# CAN_1.net
KiCad netlist of a schematic drawn in Altium Designer
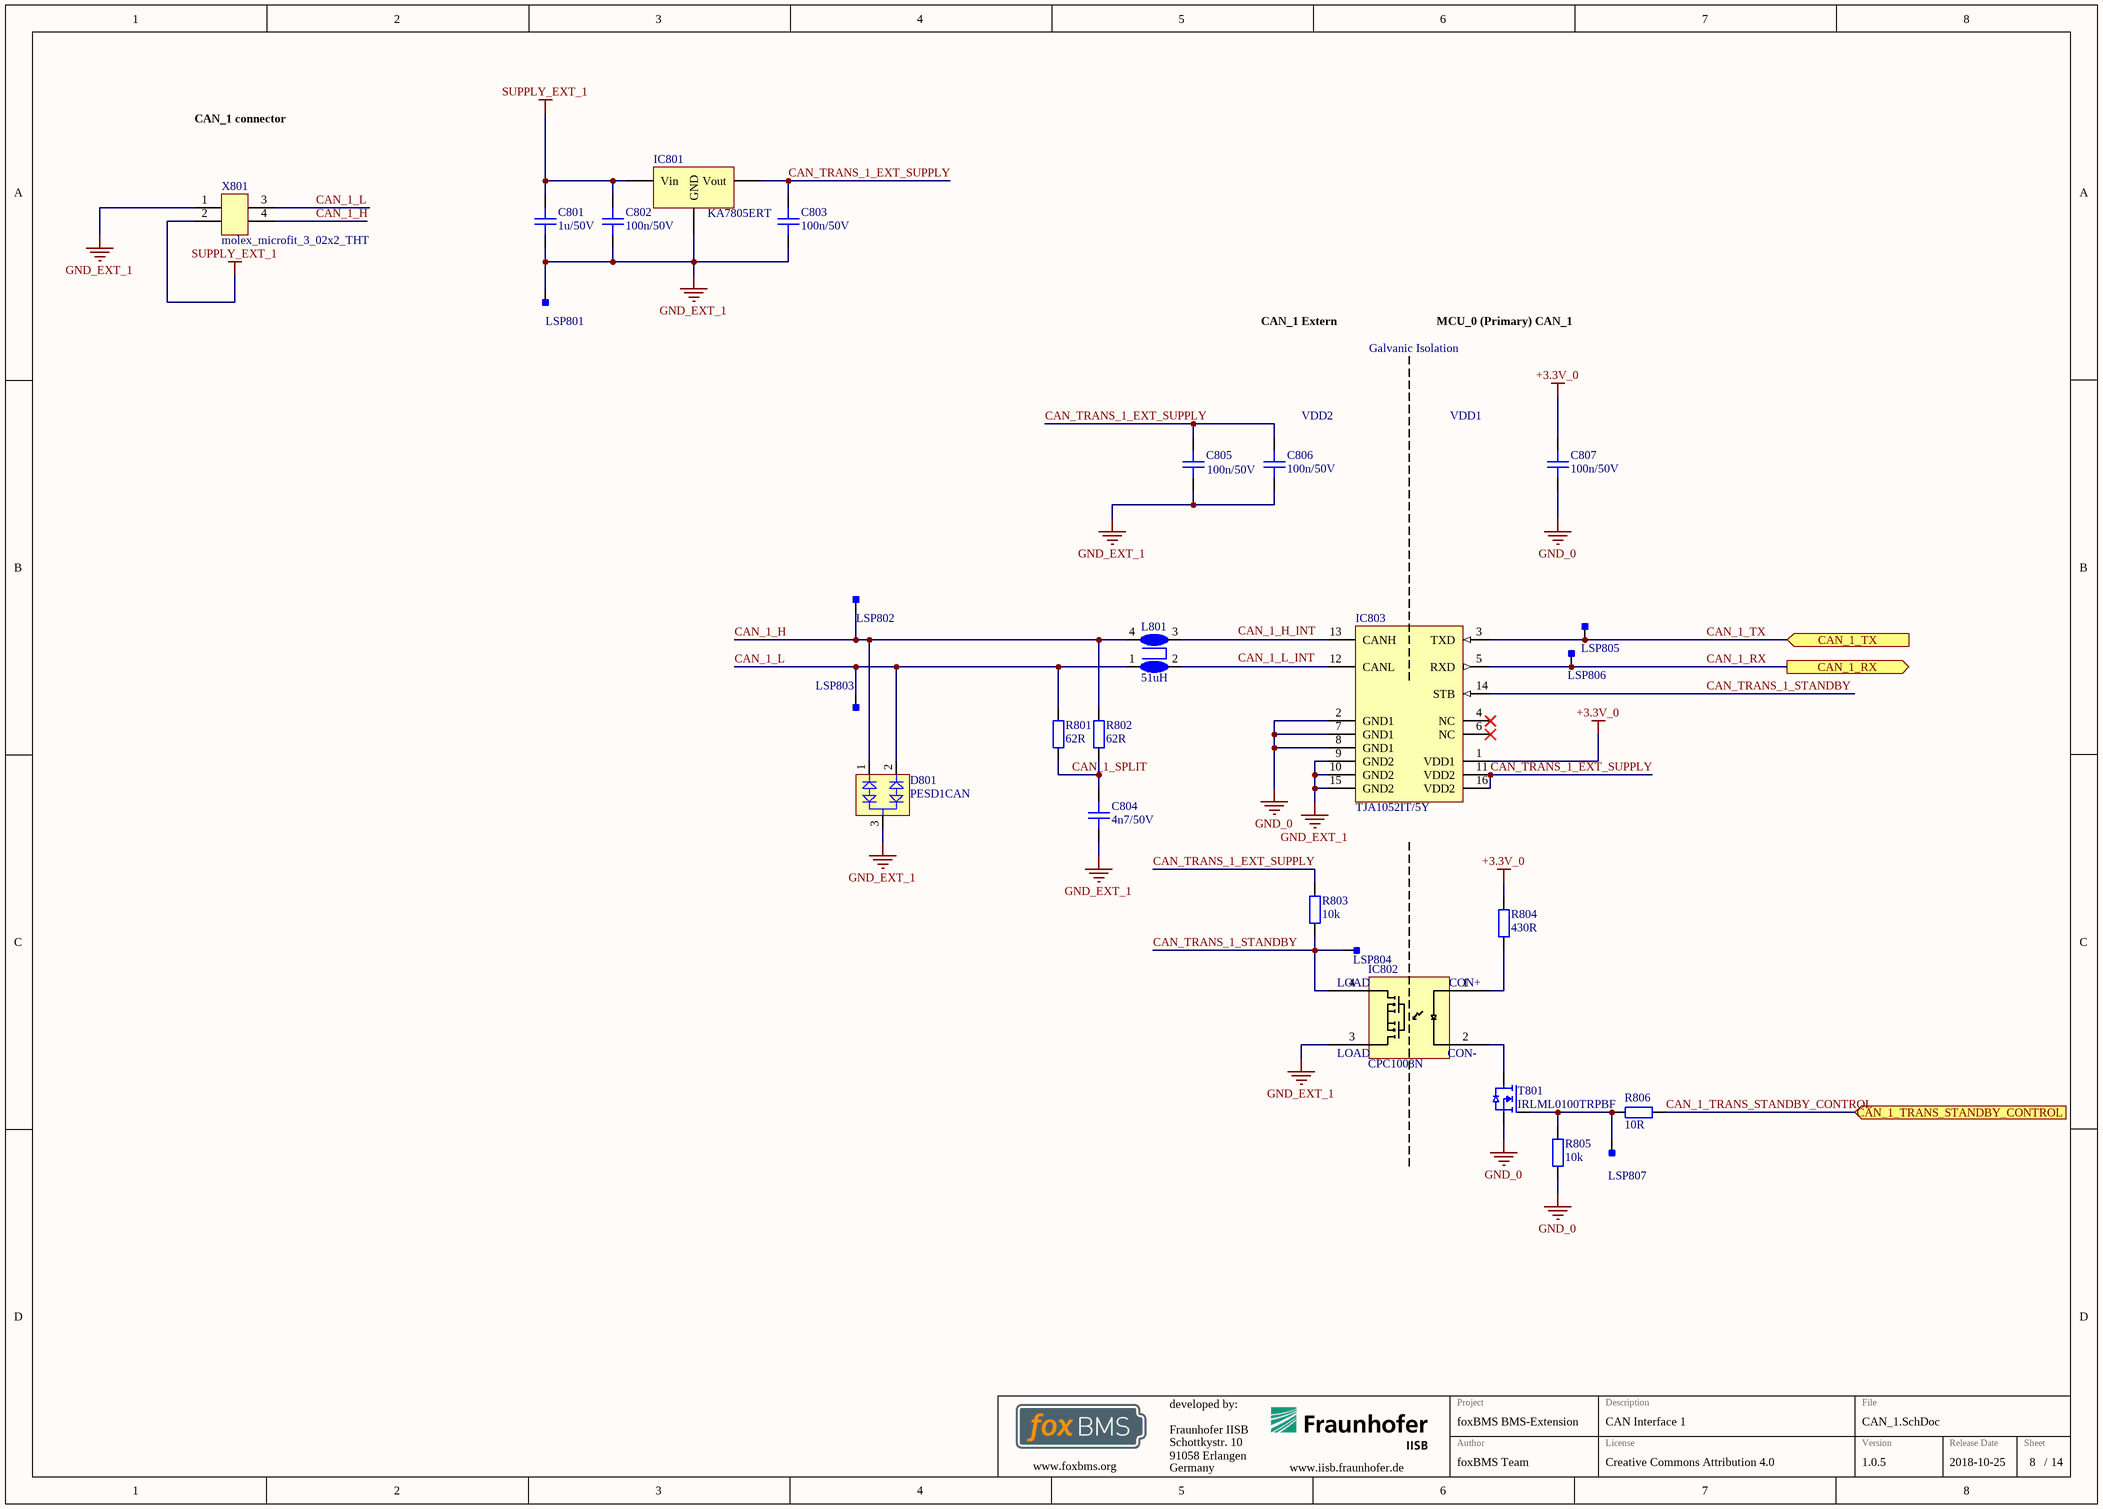
[diagram p0: CAN_1.SchDoc]

(export (version "E")
  (design (tool "Eeschema 10.0.6"))
  (components
    (comp (ref "C801")
      (value "1u/50V")
      (footprint "CAPC1608X08N")
      (description "MLCC")
      (fields (field (name "PART NUMBER") "gen_C_ceramic_1u_50V_X7R_0603") (field (name "TOLERANCE") "± 10%"))
      (libsource (lib "OE750") (part "C"))
    )
    (comp (ref "C802")
      (value "100n/50V")
      (footprint "CAPC1608X08N")
      (description "MLCC")
      (fields (field (name "PART NUMBER") "gen_C_ceramic_100n_50V_X7R_0603"))
      (libsource (lib "OE750") (part "C"))
    )
    (comp (ref "C803")
      (value "100n/50V")
      (footprint "CAPC1608X08N")
      (description "MLCC")
      (fields (field (name "PART NUMBER") "gen_C_ceramic_100n_50V_X7R_0603"))
      (libsource (lib "OE750") (part "C"))
    )
    (comp (ref "C804")
      (value "4n7/50V")
      (footprint "CAPC1608X08N")
      (description "MLCC")
      (fields (field (name "PART NUMBER") "gen_C_ceramic_4n7_50V_X7R_0603"))
      (libsource (lib "OE750") (part "C"))
    )
    (comp (ref "C805")
      (value "100n/50V")
      (footprint "CAPC1608X08N")
      (description "MLCC")
      (fields (field (name "PART NUMBER") "gen_C_ceramic_100n_50V_X7R_0603"))
      (libsource (lib "OE750") (part "C"))
    )
    (comp (ref "C806")
      (value "100n/50V")
      (footprint "CAPC1608X08N")
      (description "MLCC")
      (fields (field (name "PART NUMBER") "gen_C_ceramic_100n_50V_X7R_0603"))
      (libsource (lib "OE750") (part "C"))
    )
    (comp (ref "C807")
      (value "100n/50V")
      (footprint "CAPC1608X08N")
      (description "MLCC")
      (fields (field (name "PART NUMBER") "gen_C_ceramic_100n_50V_X7R_0603"))
      (libsource (lib "OE750") (part "C"))
    )
    (comp (ref "D801")
      (value "PESD1CAN")
      (footprint "NXP-SOT23-3_V")
      (description "CAN Bus ESD Protection Diode, 200 W, 24 V, -65 to 150 degC, 3-Pin SOT23, RoHS, Tape and Reel")
      (fields (field (name "MANUFACTURER") "NXP Semiconductors"))
      (libsource (lib "Altium Content Vault") (part "NXP-PESD1CAN-SOT23-3"))
    )
    (comp (ref "IC801")
      (value "KA7805ERT")
      (footprint "DPAK228P950X240-3N")
      (description "3-Terminal 1 A Positive Voltage Regulator")
      (fields (field (name "PART NUMBER") "KA7805ERTF") (field (name "MANUFACTURER") "Fairchild"))
      (libsource (lib "OE750") (part "KA7805ERT"))
    )
    (comp (ref "IC802")
      (value "CPC1008N")
      (footprint "SOP254P610X218-4N")
      (description "Single-Pole, Normally Open 4-Pin SOP OptoMOS Relay")
      (fields (field (name "MANUFACTURER") "CLARE"))
      (libsource (lib "OE750") (part "CPC1008N"))
    )
    (comp (ref "IC803")
      (value "TJA1052IT/5Y")
      (footprint "NXP-SOIC-16_L")
      (fields (field (name "MANUFACTURER") "NXPSemiconductors"))
      (libsource (lib "Altium Content Vault") (part "NXP-TJA1052IT-SOIC-16"))
    )
    (comp (ref "L801")
      (value "51uH")
      (footprint "B82789C0/S0")
      (description "Common Mode Choke")
      (fields (field (name "PART NUMBER") "B82789N") (field (name "MANUFACTURER") "EPCOS / TDK"))
      (libsource (lib "OE750") (part "L_CM"))
    )
    (comp (ref "LSP801")
      (value "Testpoint_Square")
      (footprint "Testpoint_S1")
      (description "Testpoint, square")
      (libsource (lib "OE750") (part "Testpoint_Square"))
    )
    (comp (ref "LSP802")
      (value "Testpoint_Square")
      (footprint "Testpoint_S1")
      (description "Testpoint, square")
      (libsource (lib "OE750") (part "Testpoint_Square"))
    )
    (comp (ref "LSP803")
      (value "Testpoint_Square")
      (footprint "Testpoint_S1")
      (description "Testpoint, square")
      (libsource (lib "OE750") (part "Testpoint_Square"))
    )
    (comp (ref "LSP804")
      (value "Testpoint_Square")
      (footprint "Testpoint_S1")
      (description "Testpoint, square")
      (libsource (lib "OE750") (part "Testpoint_Square"))
    )
    (comp (ref "LSP805")
      (value "Testpoint_Square")
      (footprint "Testpoint_S1")
      (description "Testpoint, square")
      (libsource (lib "OE750") (part "Testpoint_Square"))
    )
    (comp (ref "LSP806")
      (value "Testpoint_Square")
      (footprint "Testpoint_S1")
      (description "Testpoint, square")
      (libsource (lib "OE750") (part "Testpoint_Square"))
    )
    (comp (ref "LSP807")
      (value "Testpoint_Square")
      (footprint "Testpoint_S1")
      (description "Testpoint, square")
      (libsource (lib "OE750") (part "Testpoint_Square"))
    )
    (comp (ref "R801")
      (value "62R")
      (footprint "RESC1608X05N")
      (description "SMD Resistor 62R 0603")
      (fields (field (name "PART NUMBER") "gen_R_62R_0603") (field (name "TOLERANCE") "1%"))
      (libsource (lib "OE750") (part "R"))
    )
    (comp (ref "R802")
      (value "62R")
      (footprint "RESC1608X05N")
      (description "SMD Resistor 62R 0603")
      (fields (field (name "PART NUMBER") "gen_R_62R_0603") (field (name "TOLERANCE") "1%"))
      (libsource (lib "OE750") (part "R"))
    )
    (comp (ref "R803")
      (value "10k")
      (footprint "RESC1608X05N")
      (description "SMD Resistor 10k 0603")
      (fields (field (name "PART NUMBER") "gen_R_10k_0603") (field (name "TOLERANCE") "1%"))
      (libsource (lib "OE750") (part "R"))
    )
    (comp (ref "R804")
      (value "430R")
      (footprint "RESC1608X05N")
      (description "SMD Resistor 430R 0603")
      (fields (field (name "PART NUMBER") "gen_R_430R_0603") (field (name "TOLERANCE") "1%"))
      (libsource (lib "OE750") (part "R"))
    )
    (comp (ref "R805")
      (value "10k")
      (footprint "RESC1608X05N")
      (description "SMD Resistor 10k 0603")
      (fields (field (name "PART NUMBER") "gen_R_10k_0603") (field (name "TOLERANCE") "1%"))
      (libsource (lib "OE750") (part "R"))
    )
    (comp (ref "R806")
      (value "10R")
      (footprint "RESC1608X05N")
      (description "SMD Resistor 10R 0603")
      (fields (field (name "PART NUMBER") "gen_R_10R_0603") (field (name "TOLERANCE") "1%"))
      (libsource (lib "OE750") (part "R"))
    )
    (comp (ref "T801")
      (value "IRLML0100TRPBF")
      (footprint "SOT95P237X110-3N")
      (description "MOSFET-Transistor, n-Kanal, 1.6 A, 100 V, 0.178 ohm, 10 V, 2.5 V")
      (fields (field (name "MANUFACTURER") "Infineon"))
      (libsource (lib "OE750") (part "NMOS"))
    )
    (comp (ref "X801")
      (value "molex_microfit_3_02x2_THT")
      (footprint "43045-0421")
      (fields (field (name "MANUFACTURER") "Molex"))
      (libsource (lib "OE750") (part "X2x2"))
    )
  )
  (nets
    (net (code "1") (name "+3.3V_0") (class "Default")
      (node (ref "C807") (pin "2") (pinfunction "2_2") (pintype "passive"))
      (node (ref "IC803") (pin "1") (pinfunction "VDD1_1") (pintype "power_in"))
      (node (ref "R804") (pin "1") (pinfunction "1_1") (pintype "passive"))
    )
    (net (code "2") (name "/CAN_1_H") (class "Default")
      (node (ref "D801") (pin "1") (pinfunction "K1_1") (pintype "passive"))
      (node (ref "L801") (pin "4") (pinfunction "4_4") (pintype "passive"))
      (node (ref "LSP802") (pin "1") (pinfunction "1_1") (pintype "passive"))
      (node (ref "R802") (pin "2") (pinfunction "2_2") (pintype "passive"))
      (node (ref "X801") (pin "4") (pintype "passive"))
    )
    (net (code "4") (name "/CAN_1_L") (class "Default")
      (node (ref "D801") (pin "2") (pinfunction "K2_2") (pintype "passive"))
      (node (ref "L801") (pin "1") (pinfunction "1_1") (pintype "passive"))
      (node (ref "LSP803") (pin "1") (pinfunction "1_1") (pintype "passive"))
      (node (ref "R801") (pin "1") (pinfunction "1_1") (pintype "passive"))
      (node (ref "X801") (pin "3") (pintype "passive"))
    )
    (net (code "6") (name "/CAN_1_RX") (class "Default")
      (node (ref "IC803") (pin "5") (pinfunction "RXD_5") (pintype "output"))
      (node (ref "LSP806") (pin "1") (pinfunction "1_1") (pintype "passive"))
    )
    (net (code "7") (name "/CAN_1_SPLIT") (class "Default")
      (node (ref "C804") (pin "1") (pinfunction "1_1") (pintype "passive"))
      (node (ref "R801") (pin "2") (pinfunction "2_2") (pintype "passive"))
      (node (ref "R802") (pin "1") (pinfunction "1_1") (pintype "passive"))
    )
    (net (code "8") (name "/CAN_1_TRANS_STANDBY_CONTROL") (class "Default")
      (node (ref "R806") (pin "2") (pinfunction "2_2") (pintype "passive"))
    )
    (net (code "9") (name "/CAN_1_TX") (class "Default")
      (node (ref "IC803") (pin "3") (pinfunction "TXD_3") (pintype "input"))
      (node (ref "LSP805") (pin "1") (pinfunction "1_1") (pintype "passive"))
    )
    (net (code "10") (name "/CAN_TRANS_1_EXT_SUPPLY") (class "Default")
      (node (ref "C803") (pin "2") (pinfunction "2_2") (pintype "passive"))
      (node (ref "C805") (pin "2") (pinfunction "2_2") (pintype "passive"))
      (node (ref "C806") (pin "2") (pinfunction "2_2") (pintype "passive"))
      (node (ref "IC801") (pin "3") (pinfunction "Vout_3") (pintype "power_in"))
      (node (ref "IC803") (pin "11") (pinfunction "VDD2_11") (pintype "power_in"))
      (node (ref "IC803") (pin "16") (pinfunction "VDD2_16") (pintype "power_in"))
      (node (ref "R803") (pin "1") (pinfunction "1_1") (pintype "passive"))
    )
    (net (code "11") (name "/CAN_TRANS_1_STANDBY") (class "Default")
      (node (ref "IC802") (pin "4") (pintype "passive"))
      (node (ref "IC803") (pin "14") (pinfunction "STB_14") (pintype "input"))
      (node (ref "LSP804") (pin "1") (pinfunction "1_1") (pintype "passive"))
      (node (ref "R803") (pin "2") (pinfunction "2_2") (pintype "passive"))
    )
    (net (code "12") (name "GND_0") (class "Default")
      (node (ref "C807") (pin "1") (pinfunction "1_1") (pintype "passive"))
      (node (ref "IC803") (pin "2") (pinfunction "GND1_2") (pintype "power_in"))
      (node (ref "IC803") (pin "7") (pinfunction "GND1_7") (pintype "power_in"))
      (node (ref "IC803") (pin "8") (pinfunction "GND1_8") (pintype "power_in"))
      (node (ref "R805") (pin "2") (pinfunction "2_2") (pintype "passive"))
      (node (ref "T801") (pin "S") (pinfunction "S_S") (pintype "passive"))
    )
    (net (code "13") (name "GND_EXT_1") (class "Default")
      (node (ref "C801") (pin "1") (pinfunction "1_1") (pintype "passive"))
      (node (ref "C802") (pin "1") (pinfunction "1_1") (pintype "passive"))
      (node (ref "C803") (pin "1") (pinfunction "1_1") (pintype "passive"))
      (node (ref "C804") (pin "2") (pinfunction "2_2") (pintype "passive"))
      (node (ref "C805") (pin "1") (pinfunction "1_1") (pintype "passive"))
      (node (ref "C806") (pin "1") (pinfunction "1_1") (pintype "passive"))
      (node (ref "D801") (pin "3") (pinfunction "C_3") (pintype "passive"))
      (node (ref "IC801") (pin "2") (pinfunction "GND_2") (pintype "power_in"))
      (node (ref "IC802") (pin "3") (pintype "passive"))
      (node (ref "IC803") (pin "10") (pinfunction "GND2_10") (pintype "power_in"))
      (node (ref "IC803") (pin "15") (pinfunction "GND2_15") (pintype "power_in"))
      (node (ref "IC803") (pin "9") (pinfunction "GND2_9") (pintype "power_in"))
      (node (ref "LSP801") (pin "1") (pinfunction "1_1") (pintype "passive"))
      (node (ref "X801") (pin "1") (pintype "passive"))
    )
    (net (code "14") (name "Net-(IC802-Pad1)") (class "Default")
      (node (ref "IC802") (pin "1") (pintype "passive"))
      (node (ref "R804") (pin "2") (pinfunction "2_2") (pintype "passive"))
    )
    (net (code "15") (name "Net-(IC802-Pad2)") (class "Default")
      (node (ref "IC802") (pin "2") (pintype "power_in"))
      (node (ref "T801") (pin "D") (pinfunction "D_D") (pintype "passive"))
    )
    (net (code "16") (name "Net-(IC803-CANH)") (class "Default")
      (node (ref "IC803") (pin "13") (pinfunction "CANH_13") (pintype "passive"))
      (node (ref "L801") (pin "3") (pinfunction "3_3") (pintype "passive"))
    )
    (net (code "17") (name "Net-(IC803-CANL)") (class "Default")
      (node (ref "IC803") (pin "12") (pinfunction "CANL_12") (pintype "passive"))
      (node (ref "L801") (pin "2") (pinfunction "2_2") (pintype "passive"))
    )
    (net (code "18") (name "Net-(LSP807-Pad1)") (class "Default")
      (node (ref "LSP807") (pin "1") (pinfunction "1_1") (pintype "passive"))
      (node (ref "R805") (pin "1") (pinfunction "1_1") (pintype "passive"))
      (node (ref "R806") (pin "1") (pinfunction "1_1") (pintype "passive"))
      (node (ref "T801") (pin "G") (pinfunction "G_G") (pintype "passive"))
    )
    (net (code "19") (name "SUPPLY_EXT_1") (class "Default")
      (node (ref "C801") (pin "2") (pinfunction "2_2") (pintype "passive"))
      (node (ref "C802") (pin "2") (pinfunction "2_2") (pintype "passive"))
      (node (ref "IC801") (pin "1") (pinfunction "Vin_1") (pintype "power_in"))
      (node (ref "X801") (pin "2") (pintype "passive"))
    )
    (net (code "20") (name "unconnected-(IC803-NC-Pad4)") (class "Default")
      (node (ref "IC803") (pin "4") (pinfunction "NC_4") (pintype "passive+no_connect"))
    )
    (net (code "21") (name "unconnected-(IC803-NC-Pad6)") (class "Default")
      (node (ref "IC803") (pin "6") (pinfunction "NC_6") (pintype "passive+no_connect"))
    )
  )
)
